# W040A.net
KiCad netlist of a schematic drawn in EAGLE
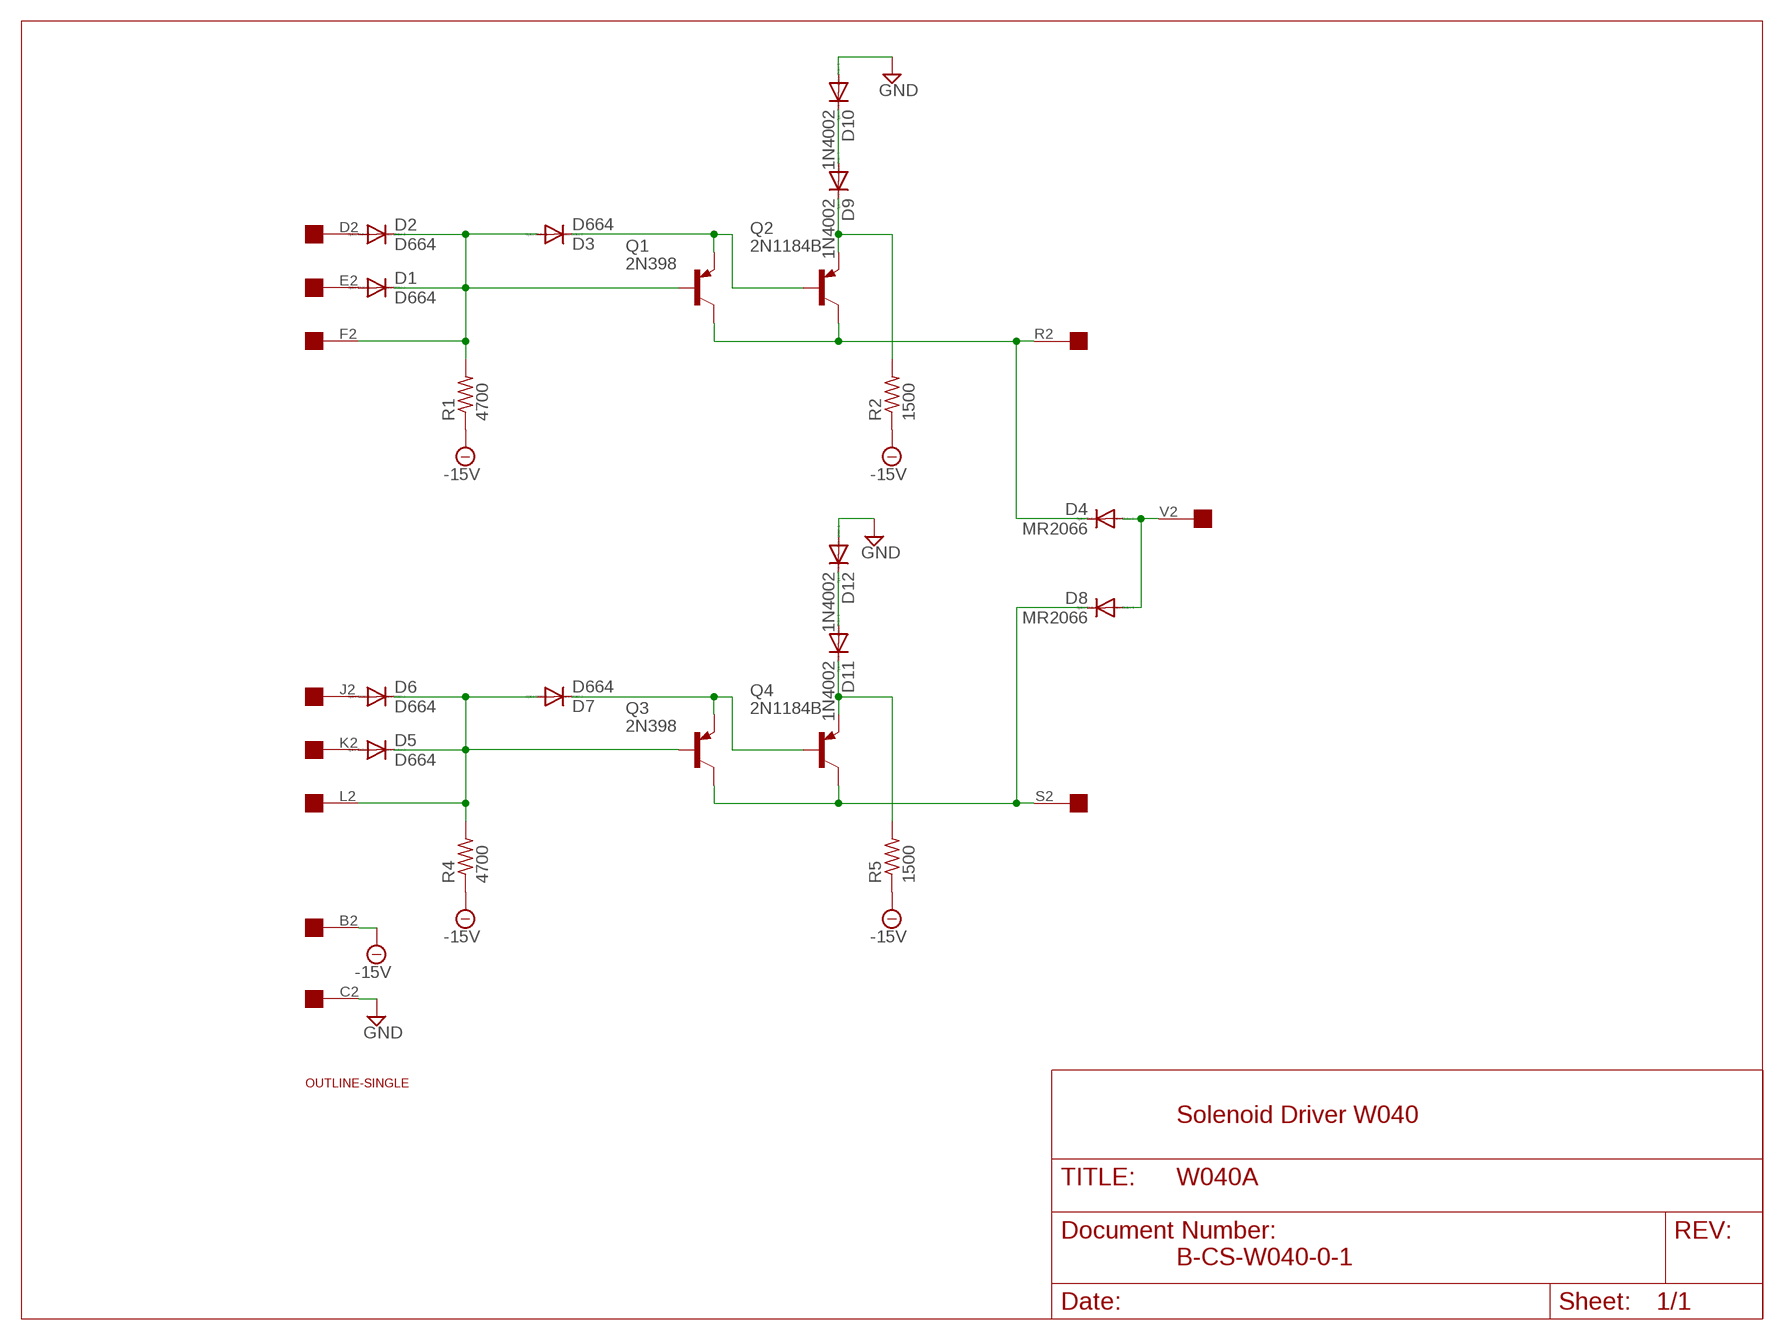
[diagram p0: schematic, sheet 1]

(export (version "E")
  (design (tool "Eeschema 10.0.6"))
  (components
    (comp (ref "D1")
      (value "D664")
      (footprint "eagle-import:DO35-10")
      (libsource (lib "eagle-import") (part "1N4148DO35-10"))
    )
    (comp (ref "D2")
      (value "D664")
      (footprint "eagle-import:DO35-10")
      (libsource (lib "eagle-import") (part "1N4148DO35-10"))
    )
    (comp (ref "D3")
      (value "D664")
      (footprint "eagle-import:DO35-10")
      (libsource (lib "eagle-import") (part "1N4148DO35-10"))
    )
    (comp (ref "D4")
      (value "MR2066")
      (footprint "eagle-import:DO41-10")
      (libsource (lib "eagle-import") (part "1N4004"))
    )
    (comp (ref "D5")
      (value "D664")
      (footprint "eagle-import:DO35-10")
      (libsource (lib "eagle-import") (part "1N4148DO35-10"))
    )
    (comp (ref "D6")
      (value "D664")
      (footprint "eagle-import:DO35-10")
      (libsource (lib "eagle-import") (part "1N4148DO35-10"))
    )
    (comp (ref "D7")
      (value "D664")
      (footprint "eagle-import:DO35-10")
      (libsource (lib "eagle-import") (part "1N4148DO35-10"))
    )
    (comp (ref "D8")
      (value "MR2066")
      (footprint "eagle-import:DO41-10")
      (libsource (lib "eagle-import") (part "1N4004"))
    )
    (comp (ref "D9")
      (value "1N4002")
      (footprint "eagle-import:DO41-10")
      (libsource (lib "eagle-import") (part "1N4004"))
    )
    (comp (ref "D10")
      (value "1N4002")
      (footprint "eagle-import:DO41-10")
      (libsource (lib "eagle-import") (part "1N4004"))
    )
    (comp (ref "D11")
      (value "1N4002")
      (footprint "eagle-import:DO41-10")
      (libsource (lib "eagle-import") (part "1N4004"))
    )
    (comp (ref "D12")
      (value "1N4002")
      (footprint "eagle-import:DO41-10")
      (libsource (lib "eagle-import") (part "1N4004"))
    )
    (comp (ref "Q1")
      (value "2N398")
      (footprint "eagle-import:TO39")
      (libsource (lib "eagle-import") (part "2N2904"))
    )
    (comp (ref "Q2")
      (value "2N1184B")
      (footprint "eagle-import:TO5")
      (libsource (lib "eagle-import") (part "2N2905"))
    )
    (comp (ref "Q3")
      (value "2N398")
      (footprint "eagle-import:TO39")
      (libsource (lib "eagle-import") (part "2N2904"))
    )
    (comp (ref "Q4")
      (value "2N1184B")
      (footprint "eagle-import:TO5")
      (libsource (lib "eagle-import") (part "2N2905"))
    )
    (comp (ref "R1")
      (value "4700")
      (footprint "eagle-import:0207_10")
      (libsource (lib "eagle-import") (part "R-US_0207/10"))
    )
    (comp (ref "R2")
      (value "1500")
      (footprint "eagle-import:0207_10")
      (libsource (lib "eagle-import") (part "R-US_0207/10"))
    )
    (comp (ref "R4")
      (value "4700")
      (footprint "eagle-import:0207_10")
      (libsource (lib "eagle-import") (part "R-US_0207/10"))
    )
    (comp (ref "R5")
      (value "1500")
      (footprint "eagle-import:0207_10")
      (libsource (lib "eagle-import") (part "R-US_0207/10"))
    )
    (comp (ref "U$1")
      (value "OUTLINE-SINGLE")
      (footprint "eagle-import:SINGLE")
      (libsource (lib "eagle-import") (part "OUTLINE-SINGLE"))
    )
    (comp (ref "U$2")
      (value "EDGE-1")
      (footprint "eagle-import:EDGE-CON1")
      (libsource (lib "eagle-import") (part "EDGE-1"))
    )
  )
  (nets
    (net (code "1") (name "-15V") (class "Default")
      (node (ref "R1") (pin "1") (pinfunction "1_1") (pintype "passive"))
      (node (ref "R2") (pin "1") (pinfunction "1_1") (pintype "passive"))
      (node (ref "R4") (pin "1") (pinfunction "1_1") (pintype "passive"))
      (node (ref "R5") (pin "1") (pinfunction "1_1") (pintype "passive"))
      (node (ref "U$2") (pin "B2") (pinfunction "1_B2") (pintype "bidirectional"))
    )
    (net (code "2") (name "GND") (class "Default")
      (node (ref "D10") (pin "A") (pinfunction "A_A") (pintype "passive"))
      (node (ref "D12") (pin "A") (pinfunction "A_A") (pintype "passive"))
      (node (ref "U$2") (pin "C2") (pinfunction "1_C2") (pintype "bidirectional"))
    )
    (net (code "3") (name "Net-(D10-PadC)") (class "Default")
      (node (ref "D10") (pin "C") (pinfunction "C_C") (pintype "passive"))
      (node (ref "D9") (pin "A") (pinfunction "A_A") (pintype "passive"))
    )
    (net (code "4") (name "Net-(D11-PadA)") (class "Default")
      (node (ref "D11") (pin "A") (pinfunction "A_A") (pintype "passive"))
      (node (ref "D12") (pin "C") (pinfunction "C_C") (pintype "passive"))
    )
    (net (code "5") (name "Net-(Q1-B)") (class "Default")
      (node (ref "D1") (pin "C") (pinfunction "C_C") (pintype "passive"))
      (node (ref "D2") (pin "C") (pinfunction "C_C") (pintype "passive"))
      (node (ref "D3") (pin "A") (pinfunction "A_A") (pintype "passive"))
      (node (ref "Q1") (pin "2") (pinfunction "B_2") (pintype "passive"))
      (node (ref "R1") (pin "2") (pinfunction "2_2") (pintype "passive"))
      (node (ref "U$2") (pin "F2") (pinfunction "1_F2") (pintype "bidirectional"))
    )
    (net (code "6") (name "Net-(Q1-C)") (class "Default")
      (node (ref "D4") (pin "C") (pinfunction "C_C") (pintype "passive"))
      (node (ref "Q1") (pin "3") (pinfunction "C_3") (pintype "passive"))
      (node (ref "Q2") (pin "3") (pinfunction "C_3") (pintype "passive"))
      (node (ref "U$2") (pin "R2") (pinfunction "1_R2") (pintype "bidirectional"))
    )
    (net (code "7") (name "Net-(Q1-E)") (class "Default")
      (node (ref "D3") (pin "C") (pinfunction "C_C") (pintype "passive"))
      (node (ref "Q1") (pin "1") (pinfunction "E_1") (pintype "passive"))
      (node (ref "Q2") (pin "2") (pinfunction "B_2") (pintype "passive"))
    )
    (net (code "8") (name "Net-(Q2-E)") (class "Default")
      (node (ref "D9") (pin "C") (pinfunction "C_C") (pintype "passive"))
      (node (ref "Q2") (pin "1") (pinfunction "E_1") (pintype "passive"))
      (node (ref "R2") (pin "2") (pinfunction "2_2") (pintype "passive"))
    )
    (net (code "9") (name "Net-(Q3-B)") (class "Default")
      (node (ref "D5") (pin "C") (pinfunction "C_C") (pintype "passive"))
      (node (ref "D6") (pin "C") (pinfunction "C_C") (pintype "passive"))
      (node (ref "D7") (pin "A") (pinfunction "A_A") (pintype "passive"))
      (node (ref "Q3") (pin "2") (pinfunction "B_2") (pintype "passive"))
      (node (ref "R4") (pin "2") (pinfunction "2_2") (pintype "passive"))
      (node (ref "U$2") (pin "L2") (pinfunction "1_L2") (pintype "bidirectional"))
    )
    (net (code "10") (name "Net-(Q3-C)") (class "Default")
      (node (ref "D8") (pin "C") (pinfunction "C_C") (pintype "passive"))
      (node (ref "Q3") (pin "3") (pinfunction "C_3") (pintype "passive"))
      (node (ref "Q4") (pin "3") (pinfunction "C_3") (pintype "passive"))
      (node (ref "U$2") (pin "S2") (pinfunction "1_S2") (pintype "bidirectional"))
    )
    (net (code "11") (name "Net-(Q3-E)") (class "Default")
      (node (ref "D7") (pin "C") (pinfunction "C_C") (pintype "passive"))
      (node (ref "Q3") (pin "1") (pinfunction "E_1") (pintype "passive"))
      (node (ref "Q4") (pin "2") (pinfunction "B_2") (pintype "passive"))
    )
    (net (code "12") (name "Net-(Q4-E)") (class "Default")
      (node (ref "D11") (pin "C") (pinfunction "C_C") (pintype "passive"))
      (node (ref "Q4") (pin "1") (pinfunction "E_1") (pintype "passive"))
      (node (ref "R5") (pin "2") (pinfunction "2_2") (pintype "passive"))
    )
    (net (code "13") (name "Net-(U$2D-1)") (class "Default")
      (node (ref "D2") (pin "A") (pinfunction "A_A") (pintype "passive"))
      (node (ref "U$2") (pin "D2") (pinfunction "1_D2") (pintype "bidirectional"))
    )
    (net (code "14") (name "Net-(U$2E-1)") (class "Default")
      (node (ref "D1") (pin "A") (pinfunction "A_A") (pintype "passive"))
      (node (ref "U$2") (pin "E2") (pinfunction "1_E2") (pintype "bidirectional"))
    )
    (net (code "15") (name "Net-(U$2H-1)") (class "Default")
      (node (ref "D6") (pin "A") (pinfunction "A_A") (pintype "passive"))
      (node (ref "U$2") (pin "J2") (pinfunction "1_J2") (pintype "bidirectional"))
    )
    (net (code "16") (name "Net-(U$2I-1)") (class "Default")
      (node (ref "D5") (pin "A") (pinfunction "A_A") (pintype "passive"))
      (node (ref "U$2") (pin "K2") (pinfunction "1_K2") (pintype "bidirectional"))
    )
    (net (code "17") (name "Net-(U$2R-1)") (class "Default")
      (node (ref "D4") (pin "A") (pinfunction "A_A") (pintype "passive"))
      (node (ref "D8") (pin "A") (pinfunction "A_A") (pintype "passive"))
      (node (ref "U$2") (pin "V2") (pinfunction "1_V2") (pintype "bidirectional"))
    )
  )
)
